# DAC8802.net
KiCad netlist of a schematic drawn in Altium Designer
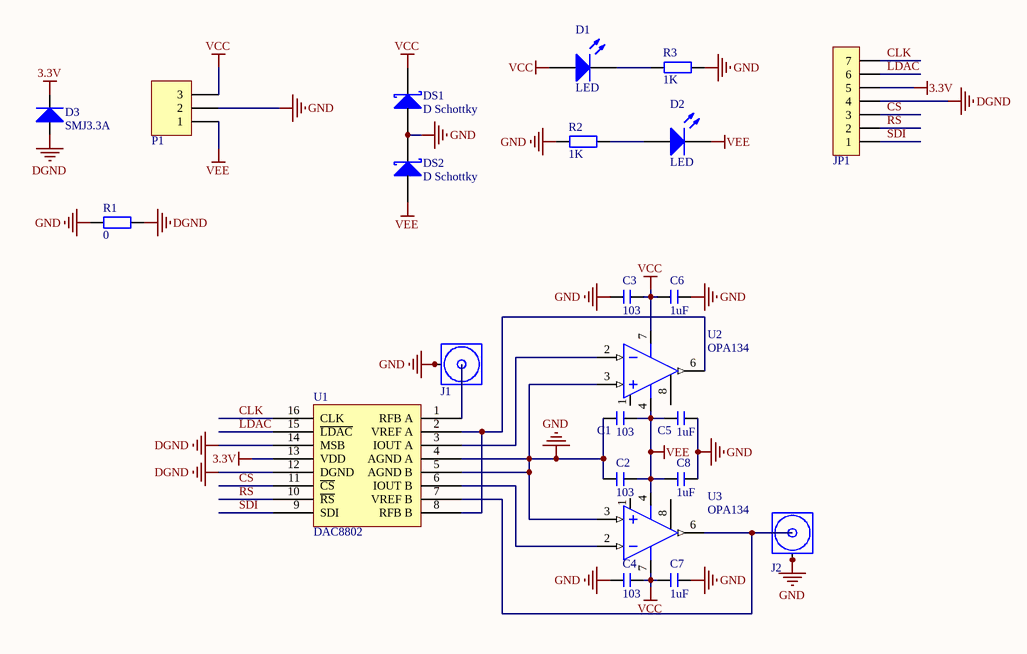
[diagram p0: DAC8802程控放大器.SchDoc]

(export (version "E")
  (design (tool "Eeschema 10.0.6"))
  (components
    (comp (ref "C1")
      (value "103")
      (footprint "C 0603")
      (description "无极性贴片电容")
      (fields (field (name "版权归属") "源创客"))
      (libsource (lib "电阻-电容-电感") (part "C"))
    )
    (comp (ref "C2")
      (value "103")
      (footprint "C 0603")
      (description "无极性贴片电容")
      (fields (field (name "版权归属") "源创客"))
      (libsource (lib "电阻-电容-电感") (part "C"))
    )
    (comp (ref "C3")
      (value "103")
      (footprint "C 0603")
      (description "无极性贴片电容")
      (fields (field (name "版权归属") "源创客"))
      (libsource (lib "电阻-电容-电感") (part "C"))
    )
    (comp (ref "C4")
      (value "103")
      (footprint "C 0603")
      (description "无极性贴片电容")
      (fields (field (name "版权归属") "源创客"))
      (libsource (lib "电阻-电容-电感") (part "C"))
    )
    (comp (ref "C5")
      (value "1uF")
      (footprint "C 0603")
      (description "无极性贴片电容")
      (fields (field (name "版权归属") "源创客"))
      (libsource (lib "电阻-电容-电感") (part "C"))
    )
    (comp (ref "C6")
      (value "1uF")
      (footprint "C 0603")
      (description "无极性贴片电容")
      (fields (field (name "版权归属") "源创客"))
      (libsource (lib "电阻-电容-电感") (part "C"))
    )
    (comp (ref "C7")
      (value "1uF")
      (footprint "C 0603")
      (description "无极性贴片电容")
      (fields (field (name "版权归属") "源创客"))
      (libsource (lib "电阻-电容-电感") (part "C"))
    )
    (comp (ref "C8")
      (value "1uF")
      (footprint "C 0603")
      (description "无极性贴片电容")
      (fields (field (name "版权归属") "源创客"))
      (libsource (lib "电阻-电容-电感") (part "C"))
    )
    (comp (ref "D1")
      (value "LED")
      (footprint "LED_0805")
      (description "发光二极管")
      (fields (field (name "PUBLISHER") "Altium Limited"))
      (libsource (lib "LIB") (part "LED"))
    )
    (comp (ref "D2")
      (value "LED")
      (footprint "LED_0805")
      (description "发光二极管")
      (fields (field (name "PUBLISHER") "Altium Limited"))
      (libsource (lib "LIB") (part "LED"))
    )
    (comp (ref "D3")
      (value "TVS")
      (footprint "DIODE-SMA")
      (description "TVS保护")
      (fields (field (name "TYPE") "SMJ3.3A") (field (name "PUBLISHER") "Altium Limited"))
      (libsource (lib "LIB") (part "TVS"))
    )
    (comp (ref "DS1")
      (value "D Schottky")
      (footprint "DIODE-SMA")
      (description "Schottky Diode")
      (fields (field (name "PUBLISHER") "Altium Limited"))
      (libsource (lib "LIB") (part "D Schottky"))
    )
    (comp (ref "DS2")
      (value "D Schottky")
      (footprint "DIODE-SMA")
      (description "Schottky Diode")
      (fields (field (name "PUBLISHER") "Altium Limited"))
      (libsource (lib "LIB") (part "D Schottky"))
    )
    (comp (ref "J1") (value "COAX") (footprint "MCX5.08-5-H") (libsource (lib "LIB") (part "COAX")))
    (comp (ref "J2") (value "COAX") (footprint "MCX5.08-5-H") (libsource (lib "LIB") (part "COAX")))
    (comp (ref "JP1")
      (value "HDR-1X7")
      (footprint "HDR-1X7")
      (description "7P接插件")
      (fields (field (name "版权归属") "源创客"))
      (libsource (lib "接插件") (part "Header 7"))
    )
    (comp (ref "P1")
      (value "Header 3")
      (footprint "HDR3X1_B2")
      (description "接插件")
      (fields (field (name "PUBLISHER") "Altium Limited"))
      (libsource (lib "LIB") (part "Header 3"))
    )
    (comp (ref "R1")
      (value "0")
      (footprint "R 0603")
      (description "贴片电阻")
      (fields (field (name "版权归属") "源创客"))
      (libsource (lib "电阻-电容-电感") (part "R"))
    )
    (comp (ref "R2")
      (value "1K")
      (footprint "R 0805")
      (description "贴片电阻")
      (fields (field (name "版权归属") "源创客"))
      (libsource (lib "电阻-电容-电感") (part "R"))
    )
    (comp (ref "R3")
      (value "1K")
      (footprint "R 0805")
      (description "贴片电阻")
      (fields (field (name "版权归属") "源创客"))
      (libsource (lib "电阻-电容-电感") (part "R"))
    )
    (comp (ref "U1")
      (value "DAC8802")
      (footprint "TSSOP16_M")
      (description "Dual.Serial Input 14Bit Multiplying Digital-to-Analog Converter")
      (libsource (lib "LIB") (part "DAC8802"))
    )
    (comp (ref "U2")
      (value "OPA134")
      (footprint "SOIC8_N")
      (description "高性能音频运算放大器")
      (libsource (lib "LIB") (part "OPA134"))
    )
    (comp (ref "U3")
      (value "OPA134")
      (footprint "SOIC8_N")
      (description "高性能音频运算放大器")
      (libsource (lib "LIB") (part "OPA134"))
    )
  )
  (nets
    (net (code "1") (name "/CLK") (class "Default")
      (node (ref "JP1") (pin "7") (pinfunction "7_7") (pintype "passive"))
      (node (ref "U1") (pin "16") (pinfunction "CLK_16") (pintype "passive"))
    )
    (net (code "2") (name "/CS") (class "Default")
      (node (ref "JP1") (pin "3") (pinfunction "3_3") (pintype "passive"))
      (node (ref "U1") (pin "11") (pinfunction "~{CS}_11") (pintype "passive"))
    )
    (net (code "3") (name "/LDAC") (class "Default")
      (node (ref "JP1") (pin "6") (pinfunction "6_6") (pintype "passive"))
      (node (ref "U1") (pin "15") (pinfunction "~{LDAC}_15") (pintype "passive"))
    )
    (net (code "4") (name "/RS") (class "Default")
      (node (ref "JP1") (pin "2") (pinfunction "2_2") (pintype "passive"))
      (node (ref "U1") (pin "10") (pinfunction "~{RS}_10") (pintype "passive"))
    )
    (net (code "5") (name "/SDI") (class "Default")
      (node (ref "JP1") (pin "1") (pinfunction "1_1") (pintype "passive"))
      (node (ref "U1") (pin "9") (pinfunction "SDI_9") (pintype "passive"))
    )
    (net (code "6") (name "3.3V") (class "Default")
      (node (ref "D3") (pin "2") (pinfunction "K_2") (pintype "passive"))
      (node (ref "JP1") (pin "5") (pinfunction "5_5") (pintype "passive"))
      (node (ref "U1") (pin "13") (pinfunction "VDD_13") (pintype "passive"))
    )
    (net (code "7") (name "DGND") (class "Default")
      (node (ref "D3") (pin "1") (pinfunction "A_1") (pintype "passive"))
      (node (ref "JP1") (pin "4") (pinfunction "4_4") (pintype "passive"))
      (node (ref "R1") (pin "2") (pinfunction "2_2") (pintype "passive"))
      (node (ref "U1") (pin "12") (pinfunction "DGND_12") (pintype "passive"))
      (node (ref "U1") (pin "14") (pinfunction "MSB_14") (pintype "passive"))
    )
    (net (code "8") (name "GND") (class "Default")
      (node (ref "C1") (pin "2") (pinfunction "2_2") (pintype "passive"))
      (node (ref "C2") (pin "2") (pinfunction "2_2") (pintype "passive"))
      (node (ref "C3") (pin "2") (pinfunction "2_2") (pintype "passive"))
      (node (ref "C4") (pin "2") (pinfunction "2_2") (pintype "passive"))
      (node (ref "C5") (pin "1") (pinfunction "1_1") (pintype "passive"))
      (node (ref "C6") (pin "1") (pinfunction "1_1") (pintype "passive"))
      (node (ref "C7") (pin "1") (pinfunction "1_1") (pintype "passive"))
      (node (ref "C8") (pin "1") (pinfunction "1_1") (pintype "passive"))
      (node (ref "DS1") (pin "1") (pinfunction "1_1") (pintype "passive"))
      (node (ref "DS2") (pin "2") (pinfunction "2_2") (pintype "passive"))
      (node (ref "J1") (pin "2") (pinfunction "GND_2") (pintype "passive"))
      (node (ref "J1") (pin "3") (pinfunction "GND_3") (pintype "passive"))
      (node (ref "J1") (pin "4") (pinfunction "GND_4") (pintype "passive"))
      (node (ref "J1") (pin "5") (pinfunction "GND_5") (pintype "passive"))
      (node (ref "J2") (pin "2") (pinfunction "GND_2") (pintype "passive"))
      (node (ref "J2") (pin "3") (pinfunction "GND_3") (pintype "passive"))
      (node (ref "J2") (pin "4") (pinfunction "GND_4") (pintype "passive"))
      (node (ref "J2") (pin "5") (pinfunction "GND_5") (pintype "passive"))
      (node (ref "P1") (pin "2") (pinfunction "2_2") (pintype "passive"))
      (node (ref "R1") (pin "1") (pinfunction "1_1") (pintype "passive"))
      (node (ref "R2") (pin "1") (pinfunction "1_1") (pintype "passive"))
      (node (ref "R3") (pin "2") (pinfunction "2_2") (pintype "passive"))
      (node (ref "U1") (pin "4") (pinfunction "AGND_A_4") (pintype "passive"))
      (node (ref "U1") (pin "5") (pinfunction "AGND_B_5") (pintype "passive"))
      (node (ref "U2") (pin "3") (pinfunction "IN+_3") (pintype "input"))
      (node (ref "U3") (pin "3") (pinfunction "IN+_3") (pintype "input"))
    )
    (net (code "9") (name "Net-(D1-K)") (class "Default")
      (node (ref "D1") (pin "2") (pinfunction "K_2") (pintype "passive"))
      (node (ref "R3") (pin "1") (pinfunction "1_1") (pintype "passive"))
    )
    (net (code "10") (name "Net-(D2-A)") (class "Default")
      (node (ref "D2") (pin "1") (pinfunction "A_1") (pintype "passive"))
      (node (ref "R2") (pin "2") (pinfunction "2_2") (pintype "passive"))
    )
    (net (code "11") (name "Net-(J1-Signal)") (class "Default")
      (node (ref "J1") (pin "1") (pinfunction "Signal_1") (pintype "passive"))
      (node (ref "U1") (pin "1") (pinfunction "RFB_A_1") (pintype "passive"))
    )
    (net (code "12") (name "Net-(J2-Signal)") (class "Default")
      (node (ref "J2") (pin "1") (pinfunction "Signal_1") (pintype "passive"))
      (node (ref "U1") (pin "7") (pinfunction "VREF_B_7") (pintype "passive"))
      (node (ref "U3") (pin "6") (pinfunction "OUT_6") (pintype "output"))
    )
    (net (code "13") (name "Net-(U1-IOUT_A)") (class "Default")
      (node (ref "U1") (pin "3") (pinfunction "IOUT_A_3") (pintype "passive"))
      (node (ref "U2") (pin "2") (pinfunction "IN-_2") (pintype "input"))
    )
    (net (code "14") (name "Net-(U1-IOUT_B)") (class "Default")
      (node (ref "U1") (pin "6") (pinfunction "IOUT_B_6") (pintype "passive"))
      (node (ref "U3") (pin "2") (pinfunction "IN-_2") (pintype "input"))
    )
    (net (code "15") (name "Net-(U1-RFB_B)") (class "Default")
      (node (ref "U1") (pin "2") (pinfunction "VREF_A_2") (pintype "passive"))
      (node (ref "U1") (pin "8") (pinfunction "RFB_B_8") (pintype "passive"))
      (node (ref "U2") (pin "6") (pinfunction "OUT_6") (pintype "output"))
    )
    (net (code "16") (name "VCC") (class "Default")
      (node (ref "C3") (pin "1") (pinfunction "1_1") (pintype "passive"))
      (node (ref "C4") (pin "1") (pinfunction "1_1") (pintype "passive"))
      (node (ref "C6") (pin "2") (pinfunction "2_2") (pintype "passive"))
      (node (ref "C7") (pin "2") (pinfunction "2_2") (pintype "passive"))
      (node (ref "D1") (pin "1") (pinfunction "A_1") (pintype "passive"))
      (node (ref "DS1") (pin "2") (pinfunction "2_2") (pintype "passive"))
      (node (ref "P1") (pin "3") (pinfunction "3_3") (pintype "passive"))
      (node (ref "U2") (pin "7") (pinfunction "V+_7") (pintype "power_in"))
      (node (ref "U3") (pin "7") (pinfunction "V+_7") (pintype "power_in"))
    )
    (net (code "17") (name "VEE") (class "Default")
      (node (ref "C1") (pin "1") (pinfunction "1_1") (pintype "passive"))
      (node (ref "C2") (pin "1") (pinfunction "1_1") (pintype "passive"))
      (node (ref "C5") (pin "2") (pinfunction "2_2") (pintype "passive"))
      (node (ref "C8") (pin "2") (pinfunction "2_2") (pintype "passive"))
      (node (ref "D2") (pin "2") (pinfunction "K_2") (pintype "passive"))
      (node (ref "DS2") (pin "1") (pinfunction "1_1") (pintype "passive"))
      (node (ref "P1") (pin "1") (pinfunction "1_1") (pintype "passive"))
      (node (ref "U2") (pin "4") (pinfunction "V-_4") (pintype "power_in"))
      (node (ref "U3") (pin "4") (pinfunction "V-_4") (pintype "power_in"))
    )
    (net (code "18") (name "unconnected-(U2-OFFSET_N1-Pad1)") (class "Default")
      (node (ref "U2") (pin "1") (pinfunction "OFFSET_N1_1") (pintype "passive"))
    )
    (net (code "19") (name "unconnected-(U2-OFFSET_N2-Pad8)") (class "Default")
      (node (ref "U2") (pin "8") (pinfunction "OFFSET_N2_8") (pintype "passive"))
    )
    (net (code "20") (name "unconnected-(U3-OFFSET_N1-Pad1)") (class "Default")
      (node (ref "U3") (pin "1") (pinfunction "OFFSET_N1_1") (pintype "passive"))
    )
    (net (code "21") (name "unconnected-(U3-OFFSET_N2-Pad8)") (class "Default")
      (node (ref "U3") (pin "8") (pinfunction "OFFSET_N2_8") (pintype "passive"))
    )
  )
)
